# top.net
KiCad netlist of a schematic drawn in Altium Designer
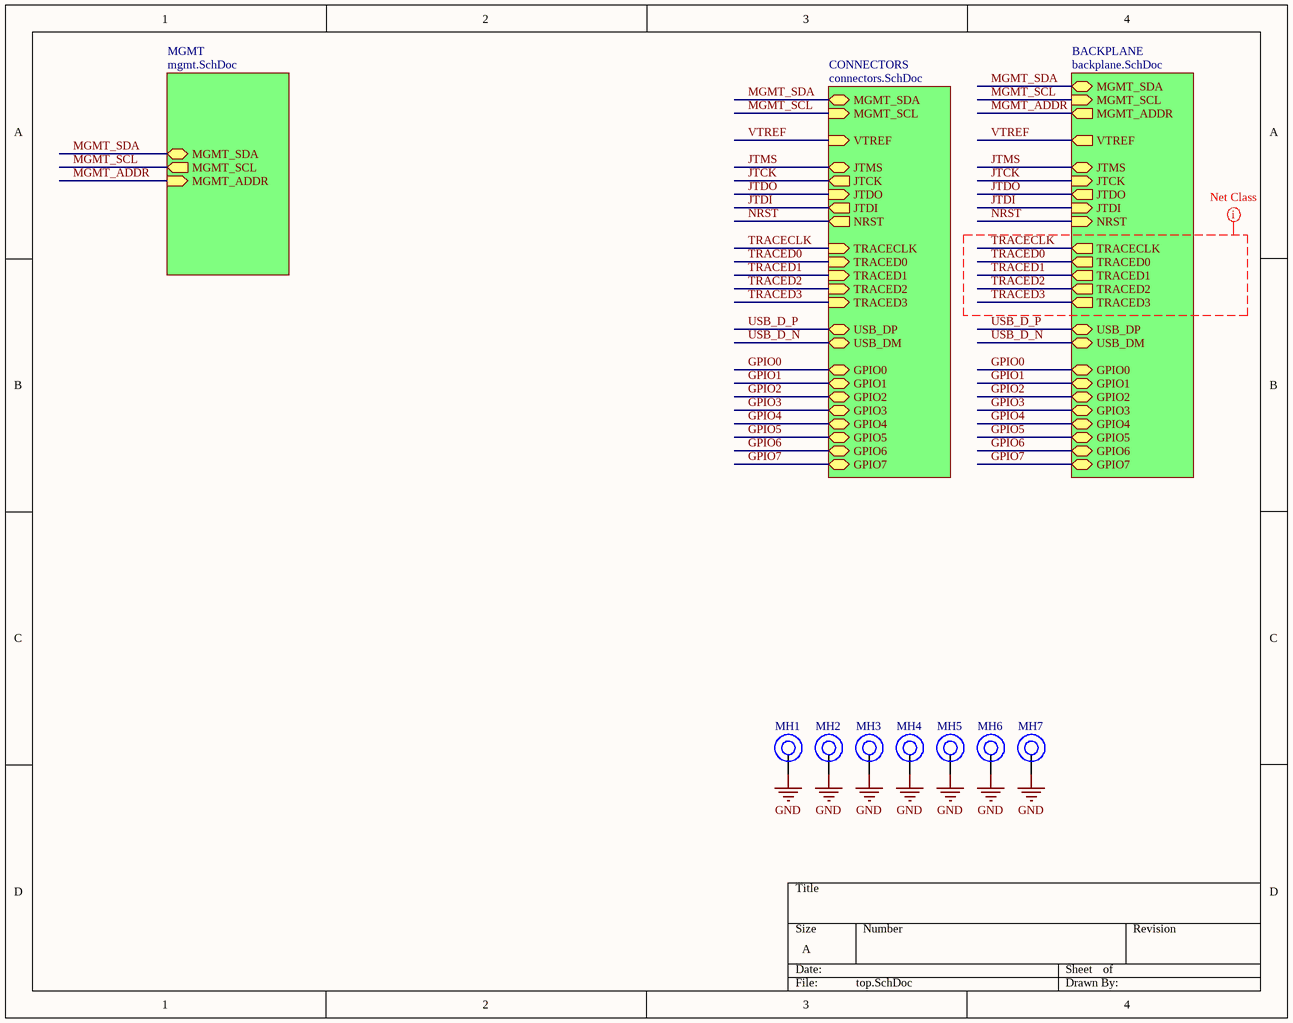
[diagram p0: top.SchDoc]

(export (version "E")
  (design (tool "Eeschema 10.0.6"))
  (components
    (comp (ref "MH1")
      (value "Mounting_Hole")
      (footprint "WA-SMSI_M2.5")
      (libsource (lib "misc") (part "Mounting_Hole"))
    )
    (comp (ref "MH2")
      (value "Mounting_Hole")
      (footprint "WA-SMSI_M2.5")
      (libsource (lib "misc") (part "Mounting_Hole"))
    )
    (comp (ref "MH3")
      (value "Mounting_Hole")
      (footprint "WA-SMSI_M2.5")
      (libsource (lib "misc") (part "Mounting_Hole"))
    )
    (comp (ref "MH4")
      (value "Mounting_Hole")
      (footprint "WA-SMSI_M2.5")
      (libsource (lib "misc") (part "Mounting_Hole"))
    )
    (comp (ref "MH5")
      (value "Mounting_Hole")
      (footprint "WA-SMSI_M2.5")
      (libsource (lib "misc") (part "Mounting_Hole"))
    )
    (comp (ref "MH6")
      (value "Mounting_Hole")
      (footprint "WA-SMSI_M2.5")
      (libsource (lib "misc") (part "Mounting_Hole"))
    )
    (comp (ref "MH7")
      (value "Mounting_Hole")
      (footprint "WA-SMSI_M2.5")
      (libsource (lib "misc") (part "Mounting_Hole"))
    )
  )
  (nets
    (net (code "25") (name "GND") (class "Default")
      (node (ref "MH1") (pin "1") (pintype "passive"))
      (node (ref "MH2") (pin "1") (pintype "passive"))
      (node (ref "MH3") (pin "1") (pintype "passive"))
      (node (ref "MH4") (pin "1") (pintype "passive"))
      (node (ref "MH5") (pin "1") (pintype "passive"))
      (node (ref "MH6") (pin "1") (pintype "passive"))
      (node (ref "MH7") (pin "1") (pintype "passive"))
    )
  )
)
